# Girlfriend_Tracker_V0_1.net
KiCad netlist of a schematic drawn in EAGLE
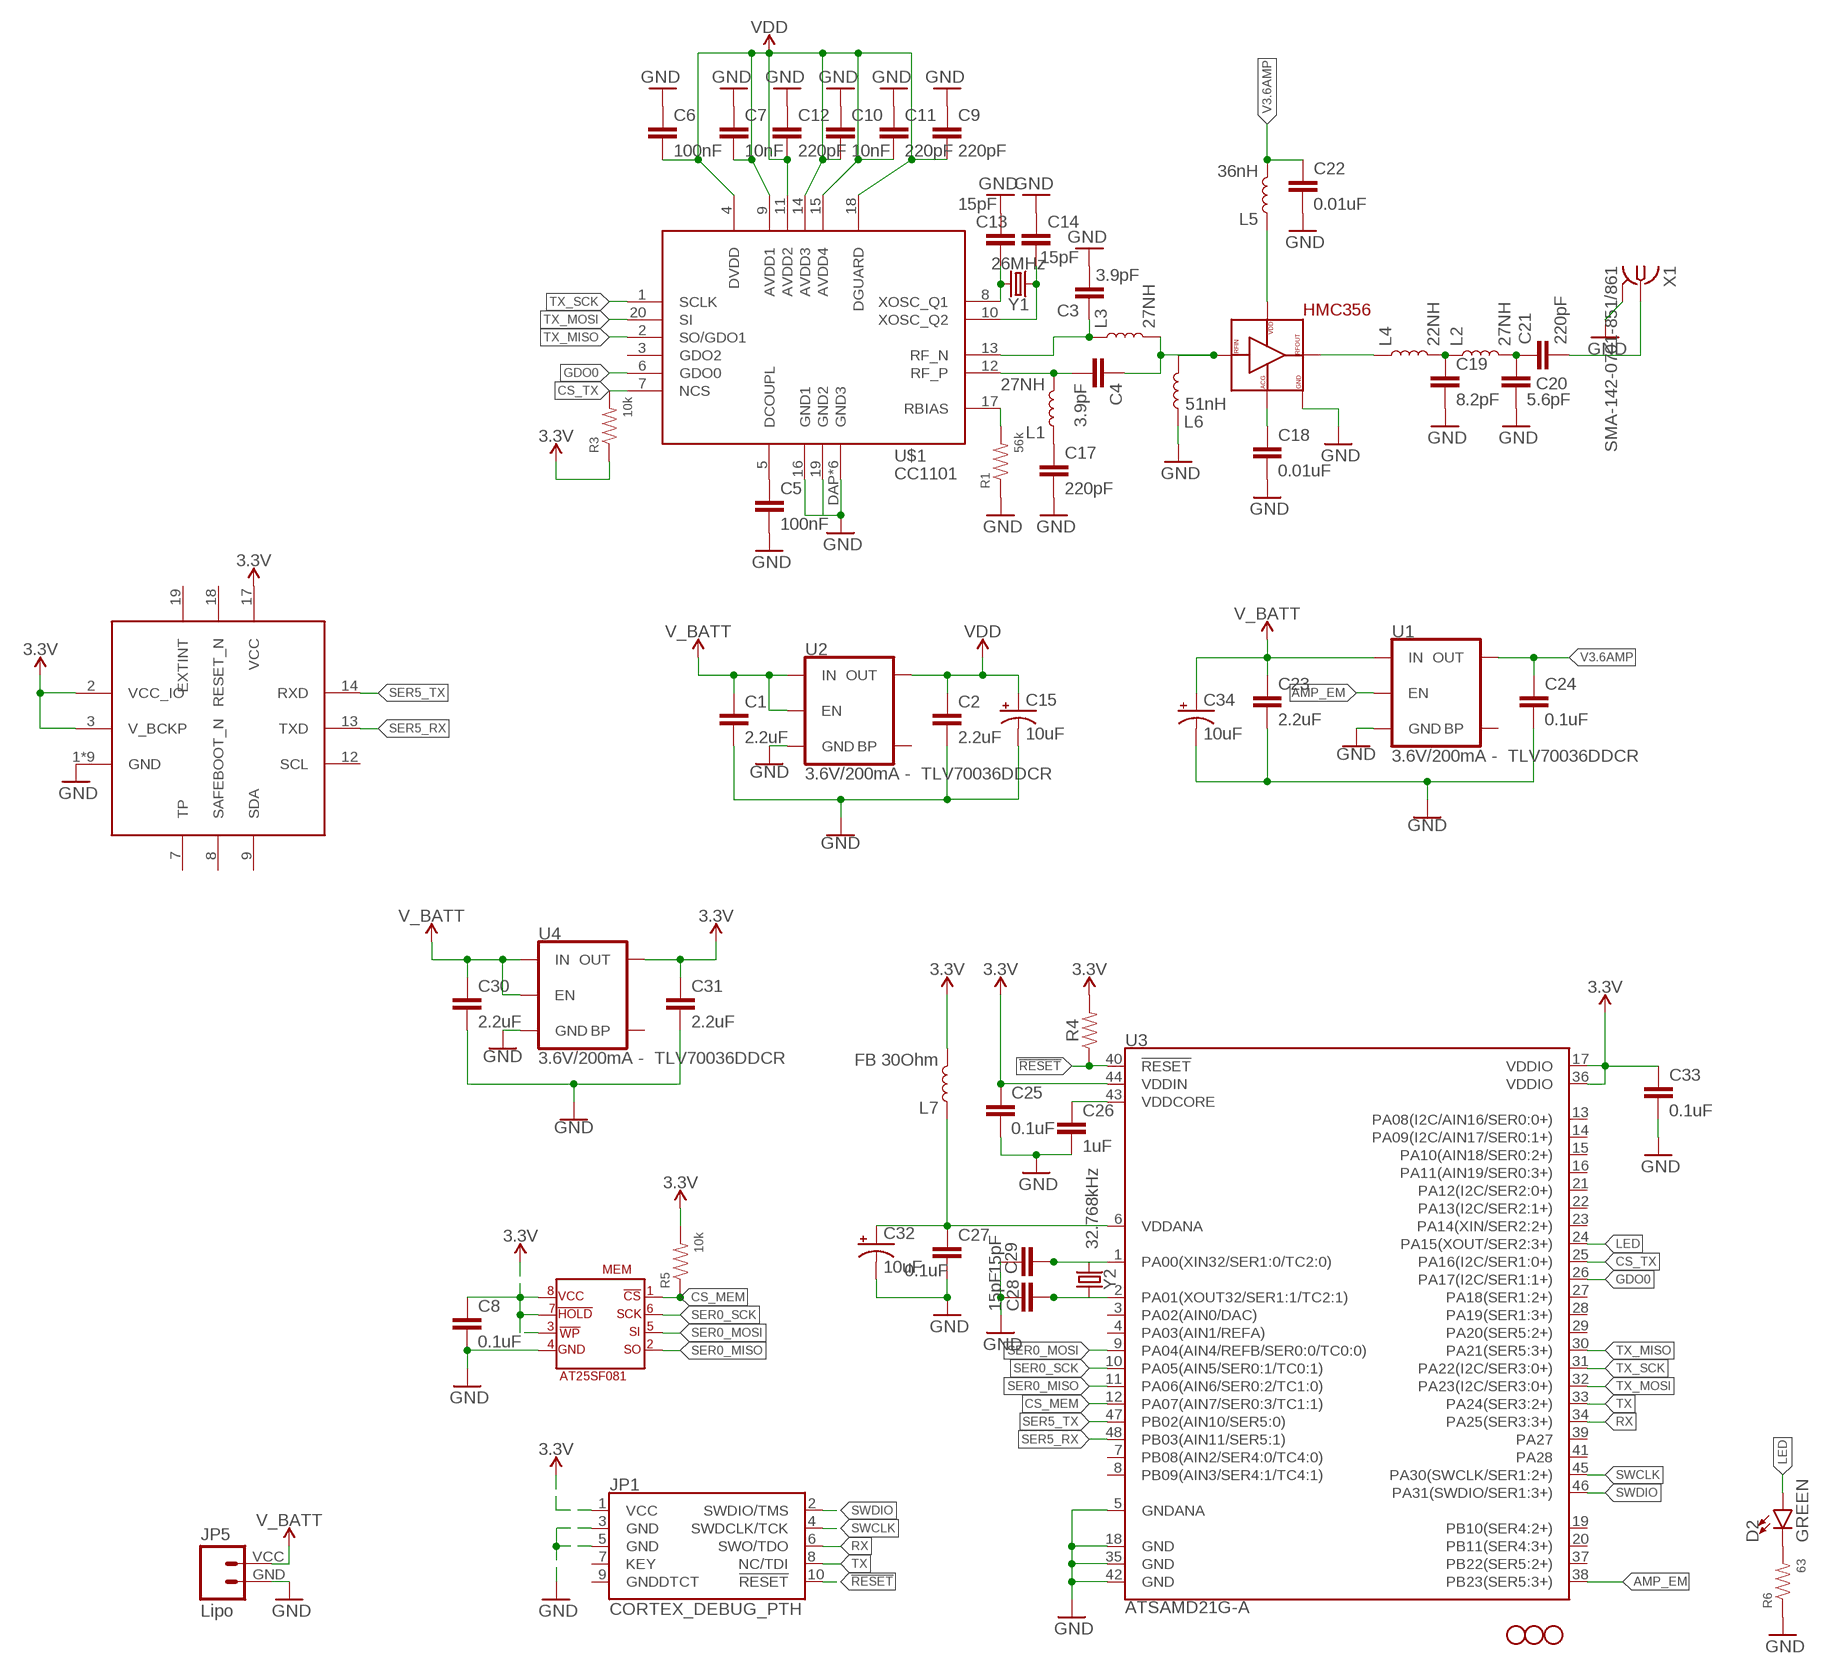
[diagram p0: schematic, sheet 1]

(export (version "E")
  (design (tool "Eeschema 10.0.6"))
  (components
    (comp (ref "C1")
      (value "2.2uF")
      (footprint "eagle-import:0603")
      (libsource (lib "eagle-import") (part "2.2UF-0603-10V-20%"))
    )
    (comp (ref "C2")
      (value "2.2uF")
      (footprint "eagle-import:0603")
      (libsource (lib "eagle-import") (part "2.2UF-0603-10V-20%"))
    )
    (comp (ref "C3")
      (value "3.9pF")
      (footprint "eagle-import:0402")
      (libsource (lib "eagle-import") (part "0.1UF-0402-16V-10%"))
    )
    (comp (ref "C4")
      (value "3.9pF")
      (footprint "eagle-import:0402")
      (libsource (lib "eagle-import") (part "0.1UF-0402-16V-10%"))
    )
    (comp (ref "C5")
      (value "100nF")
      (footprint "eagle-import:0402")
      (libsource (lib "eagle-import") (part "0.1UF-0402-16V-10%"))
    )
    (comp (ref "C6")
      (value "100nF")
      (footprint "eagle-import:0402")
      (libsource (lib "eagle-import") (part "0.1UF-0402-16V-10%"))
    )
    (comp (ref "C7")
      (value "10nF")
      (footprint "eagle-import:0402")
      (libsource (lib "eagle-import") (part "0.1UF-0402-16V-10%"))
    )
    (comp (ref "C8")
      (value "0.1uF")
      (footprint "eagle-import:0402")
      (libsource (lib "eagle-import") (part "0.1UF-0402-16V-10%"))
    )
    (comp (ref "C9")
      (value "220pF")
      (footprint "eagle-import:0402")
      (libsource (lib "eagle-import") (part "0.1UF-0402-16V-10%"))
    )
    (comp (ref "C10")
      (value "10nF")
      (footprint "eagle-import:0402")
      (libsource (lib "eagle-import") (part "0.1UF-0402-16V-10%"))
    )
    (comp (ref "C11")
      (value "220pF")
      (footprint "eagle-import:0402")
      (libsource (lib "eagle-import") (part "0.1UF-0402-16V-10%"))
    )
    (comp (ref "C12")
      (value "220pF")
      (footprint "eagle-import:0402")
      (libsource (lib "eagle-import") (part "0.1UF-0402-16V-10%"))
    )
    (comp (ref "C13")
      (value "15pF")
      (footprint "eagle-import:0402")
      (libsource (lib "eagle-import") (part "0.1UF-0402-16V-10%"))
    )
    (comp (ref "C14")
      (value "15pF")
      (footprint "eagle-import:0402")
      (libsource (lib "eagle-import") (part "0.1UF-0402-16V-10%"))
    )
    (comp (ref "C15")
      (value "10uF")
      (footprint "eagle-import:EIA3216")
      (libsource (lib "eagle-import") (part "CAP_POL1206"))
    )
    (comp (ref "C17")
      (value "220pF")
      (footprint "eagle-import:0402")
      (libsource (lib "eagle-import") (part "0.1UF-0402-16V-10%"))
    )
    (comp (ref "C18")
      (value "0.01uF")
      (footprint "eagle-import:0402")
      (libsource (lib "eagle-import") (part "0.1UF-0402-16V-10%"))
    )
    (comp (ref "C19")
      (value "8.2pF")
      (footprint "eagle-import:0402")
      (libsource (lib "eagle-import") (part "0.1UF-0402-16V-10%"))
    )
    (comp (ref "C20")
      (value "5.6pF")
      (footprint "eagle-import:0402")
      (libsource (lib "eagle-import") (part "0.1UF-0402-16V-10%"))
    )
    (comp (ref "C21")
      (value "220pF")
      (footprint "eagle-import:0402")
      (libsource (lib "eagle-import") (part "0.1UF-0402-16V-10%"))
    )
    (comp (ref "C22")
      (value "0.01uF")
      (footprint "eagle-import:0402")
      (libsource (lib "eagle-import") (part "0.1UF-0402-16V-10%"))
    )
    (comp (ref "C23")
      (value "2.2uF")
      (footprint "eagle-import:0603")
      (libsource (lib "eagle-import") (part "2.2UF-0603-10V-20%"))
    )
    (comp (ref "C24")
      (value "0.1uF")
      (footprint "eagle-import:0603")
      (libsource (lib "eagle-import") (part "2.2UF-0603-10V-20%"))
    )
    (comp (ref "C25")
      (value "0.1uF")
      (footprint "eagle-import:0402")
      (libsource (lib "eagle-import") (part "0.1UF-0402-16V-10%"))
    )
    (comp (ref "C26")
      (value "1uF")
      (footprint "eagle-import:0402")
      (libsource (lib "eagle-import") (part "0.1UF-0402-16V-10%"))
    )
    (comp (ref "C27")
      (value "0.1uF")
      (footprint "eagle-import:0402")
      (libsource (lib "eagle-import") (part "0.1UF-0402-16V-10%"))
    )
    (comp (ref "C28")
      (value "15pF")
      (footprint "eagle-import:0402")
      (libsource (lib "eagle-import") (part "15PF-0402-50V-5%"))
    )
    (comp (ref "C29")
      (value "15pF")
      (footprint "eagle-import:0402")
      (libsource (lib "eagle-import") (part "15PF-0402-50V-5%"))
    )
    (comp (ref "C30")
      (value "2.2uF")
      (footprint "eagle-import:0603")
      (libsource (lib "eagle-import") (part "2.2UF-0603-10V-20%"))
    )
    (comp (ref "C31")
      (value "2.2uF")
      (footprint "eagle-import:0603")
      (libsource (lib "eagle-import") (part "2.2UF-0603-10V-20%"))
    )
    (comp (ref "C32")
      (value "10uF")
      (footprint "eagle-import:EIA3216")
      (libsource (lib "eagle-import") (part "CAP_POL1206"))
    )
    (comp (ref "C33")
      (value "0.1uF")
      (footprint "eagle-import:0402")
      (libsource (lib "eagle-import") (part "0.1UF-0402-16V-10%"))
    )
    (comp (ref "C34")
      (value "10uF")
      (footprint "eagle-import:EIA3216")
      (libsource (lib "eagle-import") (part "CAP_POL1206"))
    )
    (comp (ref "D2")
      (value "GREEN")
      (footprint "eagle-import:LED-1206")
      (libsource (lib "eagle-import") (part "LED-GREEN1206"))
    )
    (comp (ref "H1")
      (value "STAND-OFFTIGHT")
      (footprint "eagle-import:STAND-OFF-TIGHT")
      (libsource (lib "eagle-import") (part "STAND-OFFTIGHT"))
    )
    (comp (ref "H2")
      (value "STAND-OFFTIGHT")
      (footprint "eagle-import:STAND-OFF-TIGHT")
      (libsource (lib "eagle-import") (part "STAND-OFFTIGHT"))
    )
    (comp (ref "H3")
      (value "STAND-OFFTIGHT")
      (footprint "eagle-import:STAND-OFF-TIGHT")
      (libsource (lib "eagle-import") (part "STAND-OFFTIGHT"))
    )
    (comp (ref "IC1")
      (value "SAM-M8Q")
      (footprint "eagle-import:SAM-M8Q")
      (libsource (lib "eagle-import") (part "SAM-M8Q"))
    )
    (comp (ref "JP1")
      (value "CORTEX_DEBUG_PTH")
      (footprint "eagle-import:2X5-PTH-1.27MM")
      (libsource (lib "eagle-import") (part "CORTEX_DEBUG_PTH"))
    )
    (comp (ref "JP5")
      (value "Lipo")
      (footprint "eagle-import:JST-2-SMD-VERT")
      (libsource (lib "eagle-import") (part "M024UCON-15767"))
    )
    (comp (ref "L1")
      (value "27NH")
      (footprint "eagle-import:0402")
      (libsource (lib "eagle-import") (part "SparkFun-Coils_512_INDUCTOR-0402-3.9NH"))
    )
    (comp (ref "L2")
      (value "27NH")
      (footprint "eagle-import:0402")
      (libsource (lib "eagle-import") (part "SparkFun-Coils_512_INDUCTOR-0402-3.9NH"))
    )
    (comp (ref "L3")
      (value "27NH")
      (footprint "eagle-import:0402")
      (libsource (lib "eagle-import") (part "SparkFun-Coils_512_INDUCTOR-0402-3.9NH"))
    )
    (comp (ref "L4")
      (value "22NH")
      (footprint "eagle-import:0402")
      (libsource (lib "eagle-import") (part "SparkFun-Coils_512_INDUCTOR-0402-3.9NH"))
    )
    (comp (ref "L5")
      (value "36nH")
      (footprint "eagle-import:0402")
      (libsource (lib "eagle-import") (part "SparkFun-Coils_512_INDUCTOR-0402-3.9NH"))
    )
    (comp (ref "L6")
      (value "51nH")
      (footprint "eagle-import:0402")
      (libsource (lib "eagle-import") (part "SparkFun-Coils_512_INDUCTOR-0402-3.9NH"))
    )
    (comp (ref "L7")
      (value "FB 30Ohm")
      (footprint "eagle-import:0603")
      (libsource (lib "eagle-import") (part "INDUCTOR-0603-33NH"))
    )
    (comp (ref "MEM")
      (value "AT25SF081")
      (footprint "eagle-import:AT25SF081")
      (libsource (lib "eagle-import") (part "AT25SF081"))
    )
    (comp (ref "R1")
      (value "56k")
      (footprint "eagle-import:0402")
      (libsource (lib "eagle-import") (part "RESISTOR0402"))
    )
    (comp (ref "R3")
      (value "10k")
      (footprint "eagle-import:0402")
      (libsource (lib "eagle-import") (part "RESISTOR0402"))
    )
    (comp (ref "R4")
      (value "RESISTOR0402")
      (footprint "eagle-import:0402")
      (libsource (lib "eagle-import") (part "RESISTOR0402"))
    )
    (comp (ref "R5")
      (value "10k")
      (footprint "eagle-import:0402")
      (libsource (lib "eagle-import") (part "RESISTOR0402"))
    )
    (comp (ref "R6")
      (value "63")
      (footprint "eagle-import:0402")
      (libsource (lib "eagle-import") (part "RESISTOR0402"))
    )
    (comp (ref "U$1")
      (value "CC1101")
      (footprint "eagle-import:CC1101")
      (libsource (lib "eagle-import") (part "CC1101"))
    )
    (comp (ref "U$3")
      (value "HMC356")
      (footprint "eagle-import:QFN16_HMC356")
      (libsource (lib "eagle-import") (part "HMC356"))
    )
    (comp (ref "U1")
      (value "3.6V/200mA - TLV70036DDCR")
      (footprint "eagle-import:SOT23-5")
      (libsource (lib "eagle-import") (part "V_REG_MIC52053.3V"))
    )
    (comp (ref "U2")
      (value "3.6V/200mA - TLV70036DDCR")
      (footprint "eagle-import:SOT23-5")
      (libsource (lib "eagle-import") (part "V_REG_MIC52053.3V"))
    )
    (comp (ref "U3")
      (value "ATSAMD21G-A")
      (footprint "eagle-import:TQFP-48")
      (libsource (lib "eagle-import") (part "ATSAMD21G-A"))
    )
    (comp (ref "U4")
      (value "3.6V/200mA - TLV70036DDCR")
      (footprint "eagle-import:SOT23-5")
      (libsource (lib "eagle-import") (part "V_REG_MIC52053.3V"))
    )
    (comp (ref "X1")
      (value "SMA-142-0701-851/861")
      (footprint "eagle-import:J502-ND-142-0701-851_861")
      (fields (field (name "MF") "JOHNSON COMPONENTS") (field (name "MPN") "142-0701-851"))
      (libsource (lib "eagle-import") (part "SMA-142-0701-851/861"))
    )
    (comp (ref "Y1")
      (value "26MHz")
      (footprint "eagle-import:CRYSTAL-SMD-3.2X2.5MM")
      (libsource (lib "eagle-import") (part "CRYSTALSMD-3.2X2.5"))
    )
    (comp (ref "Y2")
      (value "32.768kHz")
      (footprint "eagle-import:CRYSTAL-SMD-3.2X1.5MM")
      (libsource (lib "eagle-import") (part "CRYSTAL-32.768KHZSMD-3.2X1.5"))
    )
  )
  (nets
    (net (code "1") (name "/~{RESET}") (class "Default")
      (node (ref "JP1") (pin "10") (pinfunction "~{RESET}_10") (pintype "bidirectional"))
      (node (ref "R4") (pin "1") (pinfunction "1_1") (pintype "passive"))
      (node (ref "U3") (pin "40") (pinfunction "~{RESET}_40") (pintype "bidirectional"))
    )
    (net (code "2") (name "3.3V") (class "Default")
      (node (ref "C25") (pin "1") (pinfunction "1_1") (pintype "passive"))
      (node (ref "C31") (pin "1") (pinfunction "1_1") (pintype "passive"))
      (node (ref "C33") (pin "1") (pinfunction "1_1") (pintype "passive"))
      (node (ref "C8") (pin "1") (pinfunction "1_1") (pintype "passive"))
      (node (ref "IC1") (pin "17") (pinfunction "VCC_17") (pintype "bidirectional"))
      (node (ref "IC1") (pin "2") (pinfunction "VCC_IO_2") (pintype "bidirectional"))
      (node (ref "IC1") (pin "3") (pinfunction "V_BCKP_3") (pintype "bidirectional"))
      (node (ref "JP1") (pin "1") (pinfunction "VCC_1") (pintype "bidirectional"))
      (node (ref "L7") (pin "2") (pinfunction "2_2") (pintype "passive"))
      (node (ref "MEM") (pin "!HOLD") (pinfunction "~{HOLD}_!HOLD") (pintype "bidirectional"))
      (node (ref "MEM") (pin "!WP") (pinfunction "~{WP}_!WP") (pintype "bidirectional"))
      (node (ref "MEM") (pin "VCC") (pinfunction "VCC_VCC") (pintype "bidirectional"))
      (node (ref "R3") (pin "1") (pinfunction "1_1") (pintype "passive"))
      (node (ref "R4") (pin "2") (pinfunction "2_2") (pintype "passive"))
      (node (ref "R5") (pin "2") (pinfunction "2_2") (pintype "passive"))
      (node (ref "U3") (pin "17") (pinfunction "VDDIO_17") (pintype "bidirectional"))
      (node (ref "U3") (pin "36") (pinfunction "VDDIO_36") (pintype "bidirectional"))
      (node (ref "U3") (pin "44") (pinfunction "VDDIN_44") (pintype "bidirectional"))
      (node (ref "U4") (pin "5") (pinfunction "OUT_5") (pintype "passive"))
    )
    (net (code "3") (name "AMP_EM") (class "Default")
      (node (ref "U1") (pin "3") (pinfunction "EN_3") (pintype "input"))
      (node (ref "U3") (pin "38") (pinfunction "PB23(SER5:3+)_38") (pintype "bidirectional"))
    )
    (net (code "4") (name "CS_MEM") (class "Default")
      (node (ref "MEM") (pin "!CS") (pinfunction "~{CS}_!CS") (pintype "bidirectional"))
      (node (ref "R5") (pin "1") (pinfunction "1_1") (pintype "passive"))
      (node (ref "U3") (pin "12") (pinfunction "PA07(AIN7/SER0:3/TC1:1)_12") (pintype "bidirectional"))
    )
    (net (code "5") (name "CS_TX") (class "Default")
      (node (ref "R3") (pin "2") (pinfunction "2_2") (pintype "passive"))
      (node (ref "U$1") (pin "7") (pinfunction "NCS_7") (pintype "bidirectional"))
      (node (ref "U3") (pin "25") (pinfunction "PA16(I2C/SER1:0+)_25") (pintype "bidirectional"))
    )
    (net (code "6") (name "GDO0") (class "Default")
      (node (ref "U$1") (pin "6") (pinfunction "GDO0_6") (pintype "bidirectional"))
      (node (ref "U3") (pin "26") (pinfunction "PA17(I2C/SER1:1+)_26") (pintype "bidirectional"))
    )
    (net (code "7") (name "GND") (class "Default")
      (node (ref "C1") (pin "2") (pinfunction "2_2") (pintype "passive"))
      (node (ref "C10") (pin "1") (pinfunction "1_1") (pintype "passive"))
      (node (ref "C11") (pin "1") (pinfunction "1_1") (pintype "passive"))
      (node (ref "C12") (pin "1") (pinfunction "1_1") (pintype "passive"))
      (node (ref "C13") (pin "1") (pinfunction "1_1") (pintype "passive"))
      (node (ref "C14") (pin "2") (pinfunction "2_2") (pintype "passive"))
      (node (ref "C15") (pin "C") (pinfunction "-_C") (pintype "passive"))
      (node (ref "C17") (pin "2") (pinfunction "2_2") (pintype "passive"))
      (node (ref "C18") (pin "2") (pinfunction "2_2") (pintype "passive"))
      (node (ref "C19") (pin "2") (pinfunction "2_2") (pintype "passive"))
      (node (ref "C2") (pin "2") (pinfunction "2_2") (pintype "passive"))
      (node (ref "C20") (pin "2") (pinfunction "2_2") (pintype "passive"))
      (node (ref "C22") (pin "2") (pinfunction "2_2") (pintype "passive"))
      (node (ref "C23") (pin "2") (pinfunction "2_2") (pintype "passive"))
      (node (ref "C24") (pin "2") (pinfunction "2_2") (pintype "passive"))
      (node (ref "C25") (pin "2") (pinfunction "2_2") (pintype "passive"))
      (node (ref "C26") (pin "2") (pinfunction "2_2") (pintype "passive"))
      (node (ref "C27") (pin "2") (pinfunction "2_2") (pintype "passive"))
      (node (ref "C28") (pin "1") (pinfunction "1_1") (pintype "passive"))
      (node (ref "C29") (pin "1") (pinfunction "1_1") (pintype "passive"))
      (node (ref "C3") (pin "2") (pinfunction "2_2") (pintype "passive"))
      (node (ref "C30") (pin "2") (pinfunction "2_2") (pintype "passive"))
      (node (ref "C31") (pin "2") (pinfunction "2_2") (pintype "passive"))
      (node (ref "C32") (pin "C") (pinfunction "-_C") (pintype "passive"))
      (node (ref "C33") (pin "2") (pinfunction "2_2") (pintype "passive"))
      (node (ref "C34") (pin "C") (pinfunction "-_C") (pintype "passive"))
      (node (ref "C5") (pin "2") (pinfunction "2_2") (pintype "passive"))
      (node (ref "C6") (pin "1") (pinfunction "1_1") (pintype "passive"))
      (node (ref "C7") (pin "1") (pinfunction "1_1") (pintype "passive"))
      (node (ref "C8") (pin "2") (pinfunction "2_2") (pintype "passive"))
      (node (ref "C9") (pin "1") (pinfunction "1_1") (pintype "passive"))
      (node (ref "IC1") (pin "1") (pinfunction "GND_1") (pintype "bidirectional"))
      (node (ref "IC1") (pin "10") (pinfunction "GND_10") (pintype "bidirectional"))
      (node (ref "IC1") (pin "11") (pinfunction "GND_11") (pintype "bidirectional"))
      (node (ref "IC1") (pin "15") (pinfunction "GND_15") (pintype "bidirectional"))
      (node (ref "IC1") (pin "16") (pinfunction "GND_16") (pintype "bidirectional"))
      (node (ref "IC1") (pin "20") (pinfunction "GND_20") (pintype "bidirectional"))
      (node (ref "IC1") (pin "4") (pinfunction "GND_4") (pintype "bidirectional"))
      (node (ref "IC1") (pin "5") (pinfunction "GND_5") (pintype "bidirectional"))
      (node (ref "IC1") (pin "6") (pinfunction "GND_6") (pintype "bidirectional"))
      (node (ref "JP1") (pin "3") (pinfunction "GND_3") (pintype "bidirectional"))
      (node (ref "JP1") (pin "5") (pinfunction "GND_5") (pintype "bidirectional"))
      (node (ref "JP5") (pin "GND") (pinfunction "1_GND") (pintype "passive"))
      (node (ref "L6") (pin "1") (pinfunction "1_1") (pintype "passive"))
      (node (ref "MEM") (pin "GND") (pinfunction "GND_GND") (pintype "bidirectional"))
      (node (ref "R1") (pin "1") (pinfunction "1_1") (pintype "passive"))
      (node (ref "R6") (pin "1") (pinfunction "1_1") (pintype "passive"))
      (node (ref "U$1") (pin "16") (pinfunction "GND1_16") (pintype "bidirectional"))
      (node (ref "U$1") (pin "19") (pinfunction "GND2_19") (pintype "bidirectional"))
      (node (ref "U$1") (pin "DAP") (pinfunction "GND3_DAP") (pintype "bidirectional"))
      (node (ref "U$1") (pin "P$1") (pinfunction "GND3_P$1") (pintype "bidirectional"))
      (node (ref "U$1") (pin "P$2") (pinfunction "GND3_P$2") (pintype "bidirectional"))
      (node (ref "U$1") (pin "P$3") (pinfunction "GND3_P$3") (pintype "bidirectional"))
      (node (ref "U$1") (pin "P$4") (pinfunction "GND3_P$4") (pintype "bidirectional"))
      (node (ref "U$1") (pin "P$5") (pinfunction "GND3_P$5") (pintype "bidirectional"))
      (node (ref "U$3") (pin "P$16") (pinfunction "P$5_P$16") (pintype "bidirectional"))
      (node (ref "U$3") (pin "P$17") (pinfunction "P$5_P$17") (pintype "bidirectional"))
      (node (ref "U$3") (pin "P$17_1") (pinfunction "P$5_P$17_1") (pintype "bidirectional"))
      (node (ref "U$3") (pin "P$17_2") (pinfunction "P$5_P$17_2") (pintype "bidirectional"))
      (node (ref "U$3") (pin "P$17_3") (pinfunction "P$5_P$17_3") (pintype "bidirectional"))
      (node (ref "U$3") (pin "P$17_4") (pinfunction "P$5_P$17_4") (pintype "bidirectional"))
      (node (ref "U$3") (pin "P$2") (pinfunction "P$5_P$2") (pintype "bidirectional"))
      (node (ref "U$3") (pin "P$4") (pinfunction "P$5_P$4") (pintype "bidirectional"))
      (node (ref "U$3") (pin "P$6") (pinfunction "P$5_P$6") (pintype "bidirectional"))
      (node (ref "U1") (pin "2") (pinfunction "GND_2") (pintype "input"))
      (node (ref "U2") (pin "2") (pinfunction "GND_2") (pintype "input"))
      (node (ref "U3") (pin "18") (pinfunction "GND_18") (pintype "bidirectional"))
      (node (ref "U3") (pin "35") (pinfunction "GND_35") (pintype "bidirectional"))
      (node (ref "U3") (pin "42") (pinfunction "GND_42") (pintype "bidirectional"))
      (node (ref "U3") (pin "5") (pinfunction "GNDANA_5") (pintype "bidirectional"))
      (node (ref "U4") (pin "2") (pinfunction "GND_2") (pintype "input"))
      (node (ref "X1") (pin "G@1") (pinfunction "2_G@1") (pintype "passive"))
      (node (ref "X1") (pin "G@2") (pinfunction "2_G@2") (pintype "passive"))
      (node (ref "X1") (pin "G@3") (pinfunction "2_G@3") (pintype "passive"))
      (node (ref "X1") (pin "G@4") (pinfunction "2_G@4") (pintype "passive"))
    )
    (net (code "8") (name "LED") (class "Default")
      (node (ref "D2") (pin "A") (pinfunction "A_A") (pintype "passive"))
      (node (ref "U3") (pin "24") (pinfunction "PA15(XOUT/SER2:3+)_24") (pintype "bidirectional"))
    )
    (net (code "9") (name "Net-(C17-Pad1)") (class "Default")
      (node (ref "C17") (pin "1") (pinfunction "1_1") (pintype "passive"))
      (node (ref "L1") (pin "1") (pinfunction "1_1") (pintype "passive"))
    )
    (net (code "10") (name "Net-(C19-Pad1)") (class "Default")
      (node (ref "C19") (pin "1") (pinfunction "1_1") (pintype "passive"))
      (node (ref "L2") (pin "1") (pinfunction "1_1") (pintype "passive"))
      (node (ref "L4") (pin "2") (pinfunction "2_2") (pintype "passive"))
    )
    (net (code "11") (name "Net-(C20-Pad1)") (class "Default")
      (node (ref "C20") (pin "1") (pinfunction "1_1") (pintype "passive"))
      (node (ref "C21") (pin "1") (pinfunction "1_1") (pintype "passive"))
      (node (ref "L2") (pin "2") (pinfunction "2_2") (pintype "passive"))
    )
    (net (code "12") (name "Net-(C21-Pad2)") (class "Default")
      (node (ref "C21") (pin "2") (pinfunction "2_2") (pintype "passive"))
      (node (ref "X1") (pin "1") (pinfunction "1_1") (pintype "passive"))
    )
    (net (code "13") (name "Net-(C32-+)") (class "Default")
      (node (ref "C27") (pin "1") (pinfunction "1_1") (pintype "passive"))
      (node (ref "C32") (pin "A") (pinfunction "+_A") (pintype "passive"))
      (node (ref "L7") (pin "1") (pinfunction "1_1") (pintype "passive"))
      (node (ref "U3") (pin "6") (pinfunction "VDDANA_6") (pintype "bidirectional"))
    )
    (net (code "14") (name "Net-(D2-PadC)") (class "Default")
      (node (ref "D2") (pin "C") (pinfunction "C_C") (pintype "passive"))
      (node (ref "R6") (pin "2") (pinfunction "2_2") (pintype "passive"))
    )
    (net (code "15") (name "Net-(U$1-DCOUPL)") (class "Default")
      (node (ref "C5") (pin "1") (pinfunction "1_1") (pintype "passive"))
      (node (ref "U$1") (pin "5") (pinfunction "DCOUPL_5") (pintype "bidirectional"))
    )
    (net (code "16") (name "Net-(U$1-RBIAS)") (class "Default")
      (node (ref "R1") (pin "2") (pinfunction "2_2") (pintype "passive"))
      (node (ref "U$1") (pin "17") (pinfunction "RBIAS_17") (pintype "bidirectional"))
    )
    (net (code "17") (name "Net-(U$1-RF_N)") (class "Default")
      (node (ref "C3") (pin "1") (pinfunction "1_1") (pintype "passive"))
      (node (ref "L3") (pin "1") (pinfunction "1_1") (pintype "passive"))
      (node (ref "U$1") (pin "13") (pinfunction "RF_N_13") (pintype "bidirectional"))
    )
    (net (code "18") (name "Net-(U$1-RF_P)") (class "Default")
      (node (ref "C4") (pin "2") (pinfunction "2_2") (pintype "passive"))
      (node (ref "L1") (pin "2") (pinfunction "2_2") (pintype "passive"))
      (node (ref "U$1") (pin "12") (pinfunction "RF_P_12") (pintype "bidirectional"))
    )
    (net (code "19") (name "Net-(U$1-XOSC_Q1)") (class "Default")
      (node (ref "C13") (pin "2") (pinfunction "2_2") (pintype "passive"))
      (node (ref "U$1") (pin "8") (pinfunction "XOSC_Q1_8") (pintype "bidirectional"))
      (node (ref "Y1") (pin "3") (pinfunction "2_3") (pintype "passive"))
    )
    (net (code "20") (name "Net-(U$1-XOSC_Q2)") (class "Default")
      (node (ref "C14") (pin "1") (pinfunction "1_1") (pintype "passive"))
      (node (ref "U$1") (pin "10") (pinfunction "XOSC_Q2_10") (pintype "bidirectional"))
      (node (ref "Y1") (pin "1") (pinfunction "1_1") (pintype "passive"))
    )
    (net (code "21") (name "Net-(U$3-P$1)") (class "Default")
      (node (ref "C4") (pin "1") (pinfunction "1_1") (pintype "passive"))
      (node (ref "L3") (pin "2") (pinfunction "2_2") (pintype "passive"))
      (node (ref "L6") (pin "2") (pinfunction "2_2") (pintype "passive"))
      (node (ref "U$3") (pin "P$3") (pinfunction "P$1_P$3") (pintype "bidirectional"))
    )
    (net (code "22") (name "Net-(U$3-P$2)") (class "Default")
      (node (ref "L4") (pin "1") (pinfunction "1_1") (pintype "passive"))
      (node (ref "U$3") (pin "P$11") (pinfunction "P$2_P$11") (pintype "bidirectional"))
    )
    (net (code "23") (name "Net-(U$3-P$3)") (class "Default")
      (node (ref "C18") (pin "1") (pinfunction "1_1") (pintype "passive"))
      (node (ref "U$3") (pin "P$7") (pinfunction "P$3_P$7") (pintype "bidirectional"))
    )
    (net (code "24") (name "Net-(U$3-P$4)") (class "Default")
      (node (ref "L5") (pin "1") (pinfunction "1_1") (pintype "passive"))
      (node (ref "U$3") (pin "P$15") (pinfunction "P$4_P$15") (pintype "bidirectional"))
    )
    (net (code "25") (name "Net-(U3-PA00(XIN32{slash}SER1:0{slash}TC2:0))") (class "Default")
      (node (ref "C29") (pin "2") (pinfunction "2_2") (pintype "passive"))
      (node (ref "U3") (pin "1") (pinfunction "PA00(XIN32/SER1:0/TC2:0)_1") (pintype "bidirectional"))
      (node (ref "Y2") (pin "P$2") (pinfunction "2_P$2") (pintype "passive"))
    )
    (net (code "26") (name "Net-(U3-PA01(XOUT32{slash}SER1:1{slash}TC2:1))") (class "Default")
      (node (ref "C28") (pin "2") (pinfunction "2_2") (pintype "passive"))
      (node (ref "U3") (pin "2") (pinfunction "PA01(XOUT32/SER1:1/TC2:1)_2") (pintype "bidirectional"))
      (node (ref "Y2") (pin "P$1") (pinfunction "1_P$1") (pintype "passive"))
    )
    (net (code "27") (name "Net-(U3-VDDCORE)") (class "Default")
      (node (ref "C26") (pin "1") (pinfunction "1_1") (pintype "passive"))
      (node (ref "U3") (pin "43") (pinfunction "VDDCORE_43") (pintype "bidirectional"))
    )
    (net (code "28") (name "RX") (class "Default")
      (node (ref "JP1") (pin "6") (pinfunction "SWO/TDO_6") (pintype "bidirectional"))
      (node (ref "U3") (pin "34") (pinfunction "PA25(SER3:3+)_34") (pintype "bidirectional"))
    )
    (net (code "29") (name "SER0_MISO") (class "Default")
      (node (ref "MEM") (pin "SO") (pinfunction "SO_SO") (pintype "bidirectional"))
      (node (ref "U3") (pin "11") (pinfunction "PA06(AIN6/SER0:2/TC1:0)_11") (pintype "bidirectional"))
    )
    (net (code "30") (name "SER0_MOSI") (class "Default")
      (node (ref "MEM") (pin "SI") (pinfunction "SI_SI") (pintype "bidirectional"))
      (node (ref "U3") (pin "9") (pinfunction "PA04(AIN4/REFB/SER0:0/TC0:0)_9") (pintype "bidirectional"))
    )
    (net (code "31") (name "SER0_SCK") (class "Default")
      (node (ref "MEM") (pin "SCK") (pinfunction "SCK_SCK") (pintype "bidirectional"))
      (node (ref "U3") (pin "10") (pinfunction "PA05(AIN5/SER0:1/TC0:1)_10") (pintype "bidirectional"))
    )
    (net (code "32") (name "SER5_RX") (class "Default")
      (node (ref "IC1") (pin "13") (pinfunction "TXD_13") (pintype "bidirectional"))
      (node (ref "U3") (pin "48") (pinfunction "PB03(AIN11/SER5:1)_48") (pintype "bidirectional"))
    )
    (net (code "33") (name "SER5_TX") (class "Default")
      (node (ref "IC1") (pin "14") (pinfunction "RXD_14") (pintype "bidirectional"))
      (node (ref "U3") (pin "47") (pinfunction "PB02(AIN10/SER5:0)_47") (pintype "bidirectional"))
    )
    (net (code "34") (name "SWCLK") (class "Default")
      (node (ref "JP1") (pin "4") (pinfunction "SWDCLK/TCK_4") (pintype "bidirectional"))
      (node (ref "U3") (pin "45") (pinfunction "PA30(SWCLK/SER1:2+)_45") (pintype "bidirectional"))
    )
    (net (code "35") (name "SWDIO") (class "Default")
      (node (ref "JP1") (pin "2") (pinfunction "SWDIO/TMS_2") (pintype "bidirectional"))
      (node (ref "U3") (pin "46") (pinfunction "PA31(SWDIO/SER1:3+)_46") (pintype "bidirectional"))
    )
    (net (code "36") (name "TX") (class "Default")
      (node (ref "JP1") (pin "8") (pinfunction "NC/TDI_8") (pintype "bidirectional"))
      (node (ref "U3") (pin "33") (pinfunction "PA24(SER3:2+)_33") (pintype "bidirectional"))
    )
    (net (code "37") (name "TX_MISO") (class "Default")
      (node (ref "U$1") (pin "2") (pinfunction "SO/GDO1_2") (pintype "bidirectional"))
      (node (ref "U3") (pin "30") (pinfunction "PA21(SER5:3+)_30") (pintype "bidirectional"))
    )
    (net (code "38") (name "TX_MOSI") (class "Default")
      (node (ref "U$1") (pin "20") (pinfunction "SI_20") (pintype "bidirectional"))
      (node (ref "U3") (pin "32") (pinfunction "PA23(I2C/SER3:0+)_32") (pintype "bidirectional"))
    )
    (net (code "39") (name "TX_SCK") (class "Default")
      (node (ref "U$1") (pin "1") (pinfunction "SCLK_1") (pintype "bidirectional"))
      (node (ref "U3") (pin "31") (pinfunction "PA22(I2C/SER3:0+)_31") (pintype "bidirectional"))
    )
    (net (code "40") (name "V3.6AMP") (class "Default")
      (node (ref "C22") (pin "1") (pinfunction "1_1") (pintype "passive"))
      (node (ref "C24") (pin "1") (pinfunction "1_1") (pintype "passive"))
      (node (ref "L5") (pin "2") (pinfunction "2_2") (pintype "passive"))
      (node (ref "U1") (pin "5") (pinfunction "OUT_5") (pintype "passive"))
    )
    (net (code "41") (name "VDD") (class "Default")
      (node (ref "C10") (pin "2") (pinfunction "2_2") (pintype "passive"))
      (node (ref "C11") (pin "2") (pinfunction "2_2") (pintype "passive"))
      (node (ref "C12") (pin "2") (pinfunction "2_2") (pintype "passive"))
      (node (ref "C15") (pin "A") (pinfunction "+_A") (pintype "passive"))
      (node (ref "C2") (pin "1") (pinfunction "1_1") (pintype "passive"))
      (node (ref "C6") (pin "2") (pinfunction "2_2") (pintype "passive"))
      (node (ref "C7") (pin "2") (pinfunction "2_2") (pintype "passive"))
      (node (ref "C9") (pin "2") (pinfunction "2_2") (pintype "passive"))
      (node (ref "U$1") (pin "11") (pinfunction "AVDD2_11") (pintype "bidirectional"))
      (node (ref "U$1") (pin "14") (pinfunction "AVDD3_14") (pintype "bidirectional"))
      (node (ref "U$1") (pin "15") (pinfunction "AVDD4_15") (pintype "bidirectional"))
      (node (ref "U$1") (pin "18") (pinfunction "DGUARD_18") (pintype "bidirectional"))
      (node (ref "U$1") (pin "4") (pinfunction "DVDD_4") (pintype "bidirectional"))
      (node (ref "U$1") (pin "9") (pinfunction "AVDD1_9") (pintype "bidirectional"))
      (node (ref "U2") (pin "5") (pinfunction "OUT_5") (pintype "passive"))
    )
    (net (code "42") (name "V_BATT") (class "Default")
      (node (ref "C1") (pin "1") (pinfunction "1_1") (pintype "passive"))
      (node (ref "C23") (pin "1") (pinfunction "1_1") (pintype "passive"))
      (node (ref "C30") (pin "1") (pinfunction "1_1") (pintype "passive"))
      (node (ref "C34") (pin "A") (pinfunction "+_A") (pintype "passive"))
      (node (ref "JP5") (pin "VCC") (pinfunction "2_VCC") (pintype "passive"))
      (node (ref "U1") (pin "1") (pinfunction "IN_1") (pintype "input"))
      (node (ref "U2") (pin "1") (pinfunction "IN_1") (pintype "input"))
      (node (ref "U2") (pin "3") (pinfunction "EN_3") (pintype "input"))
      (node (ref "U4") (pin "1") (pinfunction "IN_1") (pintype "input"))
      (node (ref "U4") (pin "3") (pinfunction "EN_3") (pintype "input"))
    )
    (net (code "43") (name "unconnected-(IC1-EXTINT-Pad19)") (class "Default")
      (node (ref "IC1") (pin "19") (pinfunction "EXTINT_19") (pintype "bidirectional"))
    )
    (net (code "44") (name "unconnected-(IC1-RESET_N-Pad18)") (class "Default")
      (node (ref "IC1") (pin "18") (pinfunction "RESET_N_18") (pintype "bidirectional"))
    )
    (net (code "45") (name "unconnected-(IC1-SAFEBOOT_N-Pad8)") (class "Default")
      (node (ref "IC1") (pin "8") (pinfunction "SAFEBOOT_N_8") (pintype "bidirectional"))
    )
    (net (code "46") (name "unconnected-(IC1-SCL-Pad12)") (class "Default")
      (node (ref "IC1") (pin "12") (pinfunction "SCL_12") (pintype "bidirectional"))
    )
    (net (code "47") (name "unconnected-(IC1-SDA-Pad9)") (class "Default")
      (node (ref "IC1") (pin "9") (pinfunction "SDA_9") (pintype "bidirectional"))
    )
    (net (code "48") (name "unconnected-(IC1-TP-Pad7)") (class "Default")
      (node (ref "IC1") (pin "7") (pinfunction "TP_7") (pintype "bidirectional"))
    )
    (net (code "49") (name "unconnected-(JP1-GNDDTCT-Pad9)") (class "Default")
      (node (ref "JP1") (pin "9") (pinfunction "GNDDTCT_9") (pintype "bidirectional"))
    )
    (net (code "50") (name "unconnected-(JP1-KEY-Pad7)") (class "Default")
      (node (ref "JP1") (pin "7") (pinfunction "KEY_7") (pintype "bidirectional"))
    )
    (net (code "51") (name "unconnected-(U$1-GDO2-Pad3)") (class "Default")
      (node (ref "U$1") (pin "3") (pinfunction "GDO2_3") (pintype "bidirectional"))
    )
    (net (code "52") (name "unconnected-(U1-BP-Pad4)") (class "Default")
      (node (ref "U1") (pin "4") (pinfunction "BP_4") (pintype "input"))
    )
    (net (code "53") (name "unconnected-(U2-BP-Pad4)") (class "Default")
      (node (ref "U2") (pin "4") (pinfunction "BP_4") (pintype "input"))
    )
    (net (code "54") (name "unconnected-(U3-PA02(AIN0{slash}DAC)-Pad3)") (class "Default")
      (node (ref "U3") (pin "3") (pinfunction "PA02(AIN0/DAC)_3") (pintype "bidirectional"))
    )
    (net (code "55") (name "unconnected-(U3-PA03(AIN1{slash}REFA)-Pad4)") (class "Default")
      (node (ref "U3") (pin "4") (pinfunction "PA03(AIN1/REFA)_4") (pintype "bidirectional"))
    )
    (net (code "56") (name "unconnected-(U3-PA08(I2C{slash}AIN16{slash}SER0:0+)-Pad13)") (class "Default")
      (node (ref "U3") (pin "13") (pinfunction "PA08(I2C/AIN16/SER0:0+)_13") (pintype "bidirectional"))
    )
    (net (code "57") (name "unconnected-(U3-PA09(I2C{slash}AIN17{slash}SER0:1+)-Pad14)") (class "Default")
      (node (ref "U3") (pin "14") (pinfunction "PA09(I2C/AIN17/SER0:1+)_14") (pintype "bidirectional"))
    )
    (net (code "58") (name "unconnected-(U3-PA10(AIN18{slash}SER0:2+)-Pad15)") (class "Default")
      (node (ref "U3") (pin "15") (pinfunction "PA10(AIN18/SER0:2+)_15") (pintype "bidirectional"))
    )
    (net (code "59") (name "unconnected-(U3-PA11(AIN19{slash}SER0:3+)-Pad16)") (class "Default")
      (node (ref "U3") (pin "16") (pinfunction "PA11(AIN19/SER0:3+)_16") (pintype "bidirectional"))
    )
    (net (code "60") (name "unconnected-(U3-PA12(I2C{slash}SER2:0+)-Pad21)") (class "Default")
      (node (ref "U3") (pin "21") (pinfunction "PA12(I2C/SER2:0+)_21") (pintype "bidirectional"))
    )
    (net (code "61") (name "unconnected-(U3-PA13(I2C{slash}SER2:1+)-Pad22)") (class "Default")
      (node (ref "U3") (pin "22") (pinfunction "PA13(I2C/SER2:1+)_22") (pintype "bidirectional"))
    )
    (net (code "62") (name "unconnected-(U3-PA14(XIN{slash}SER2:2+)-Pad23)") (class "Default")
      (node (ref "U3") (pin "23") (pinfunction "PA14(XIN/SER2:2+)_23") (pintype "bidirectional"))
    )
    (net (code "63") (name "unconnected-(U3-PA18(SER1:2+)-Pad27)") (class "Default")
      (node (ref "U3") (pin "27") (pinfunction "PA18(SER1:2+)_27") (pintype "bidirectional"))
    )
    (net (code "64") (name "unconnected-(U3-PA19(SER1:3+)-Pad28)") (class "Default")
      (node (ref "U3") (pin "28") (pinfunction "PA19(SER1:3+)_28") (pintype "bidirectional"))
    )
    (net (code "65") (name "unconnected-(U3-PA20(SER5:2+)-Pad29)") (class "Default")
      (node (ref "U3") (pin "29") (pinfunction "PA20(SER5:2+)_29") (pintype "bidirectional"))
    )
    (net (code "66") (name "unconnected-(U3-PA27-Pad39)") (class "Default")
      (node (ref "U3") (pin "39") (pinfunction "PA27_39") (pintype "bidirectional"))
    )
    (net (code "67") (name "unconnected-(U3-PA28-Pad41)") (class "Default")
      (node (ref "U3") (pin "41") (pinfunction "PA28_41") (pintype "bidirectional"))
    )
    (net (code "68") (name "unconnected-(U3-PB08(AIN2{slash}SER4:0{slash}TC4:0)-Pad7)") (class "Default")
      (node (ref "U3") (pin "7") (pinfunction "PB08(AIN2/SER4:0/TC4:0)_7") (pintype "bidirectional"))
    )
    (net (code "69") (name "unconnected-(U3-PB09(AIN3{slash}SER4:1{slash}TC4:1)-Pad8)") (class "Default")
      (node (ref "U3") (pin "8") (pinfunction "PB09(AIN3/SER4:1/TC4:1)_8") (pintype "bidirectional"))
    )
    (net (code "70") (name "unconnected-(U3-PB10(SER4:2+)-Pad19)") (class "Default")
      (node (ref "U3") (pin "19") (pinfunction "PB10(SER4:2+)_19") (pintype "bidirectional"))
    )
    (net (code "71") (name "unconnected-(U3-PB11(SER4:3+)-Pad20)") (class "Default")
      (node (ref "U3") (pin "20") (pinfunction "PB11(SER4:3+)_20") (pintype "bidirectional"))
    )
    (net (code "72") (name "unconnected-(U3-PB22(SER5:2+)-Pad37)") (class "Default")
      (node (ref "U3") (pin "37") (pinfunction "PB22(SER5:2+)_37") (pintype "bidirectional"))
    )
    (net (code "73") (name "unconnected-(U4-BP-Pad4)") (class "Default")
      (node (ref "U4") (pin "4") (pinfunction "BP_4") (pintype "input"))
    )
  )
)
